# Safety_2019_V_3_0_uController.net
KiCad netlist of a schematic drawn in Altium Designer
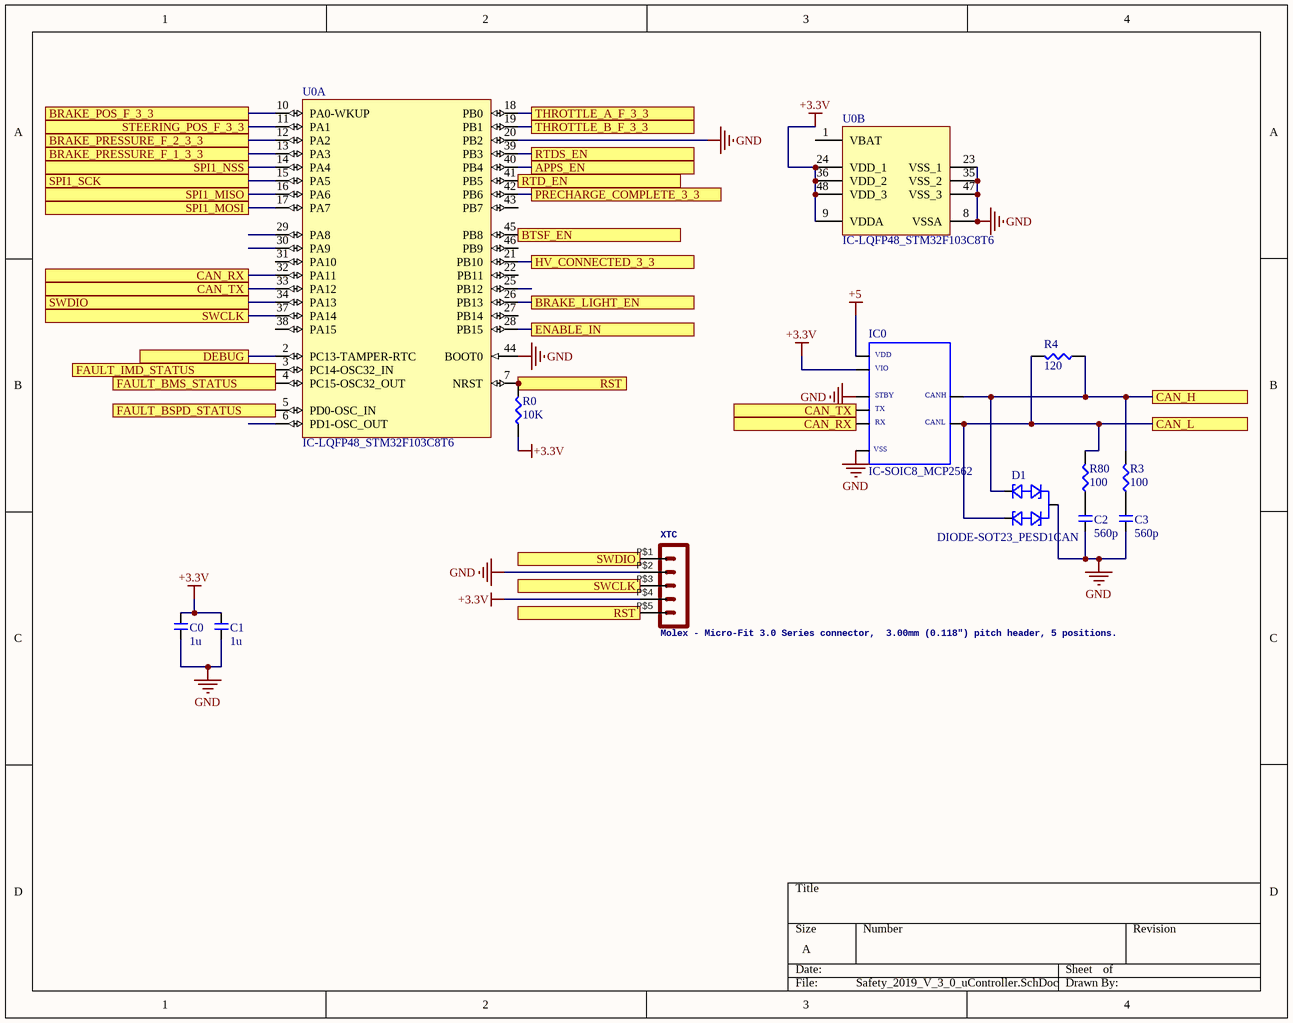
[diagram p0: Safety_2019_V_3_0_uController.SchDoc]

(export (version "E")
  (design (tool "Eeschema 10.0.6"))
  (components
    (comp (ref "C0")
      (value "1u")
      (footprint "CAP-0603")
      (libsource (lib "ife19_Elec_Library") (part "CAP-0603"))
    )
    (comp (ref "C1")
      (value "1u")
      (footprint "CAP-0603")
      (libsource (lib "ife19_Elec_Library") (part "CAP-0603"))
    )
    (comp (ref "C2")
      (value "560p")
      (footprint "CAP-0603")
      (libsource (lib "ife19_Elec_Library") (part "CAP-0603"))
    )
    (comp (ref "C3")
      (value "560p")
      (footprint "CAP-0603")
      (libsource (lib "ife19_Elec_Library") (part "CAP-0603"))
    )
    (comp (ref "D1")
      (value "DIODE-SOT23_PESD1CAN")
      (footprint "SOT23")
      (libsource (lib "ife19_Elec_Library") (part "DIODE-SOT23_PESD1CAN"))
    )
    (comp (ref "IC0")
      (value "IC-SOIC8_MCP2562")
      (footprint "SOIC8")
      (libsource (lib "ife19_Elec_Library") (part "IC-SOIC8_MCP2562"))
    )
    (comp (ref "R0")
      (value "10K")
      (footprint "RES-0603")
      (libsource (lib "ife19_Elec_Library") (part "RES-0603"))
    )
    (comp (ref "R3")
      (value "100")
      (footprint "RES-0603")
      (libsource (lib "ife19_Elec_Library") (part "RES-0603"))
    )
    (comp (ref "R4")
      (value "120")
      (footprint "RES-0603")
      (libsource (lib "ife19_Elec_Library") (part "RES-0603"))
    )
    (comp (ref "R80")
      (value "100")
      (footprint "RES-0603")
      (libsource (lib "ife19_Elec_Library") (part "RES-0603"))
    )
    (comp (ref "U0")
      (value "IC-LQFP48_STM32F103C8T6")
      (footprint "STM-LQFP48_M")
      (fields (field (name "PARTNUMBER") "STM32F103C8T6"))
      (libsource (lib "ife19_Elec_Library") (part "IC-LQFP48_STM32F103C8T6"))
    )
    (comp (ref "XTC")
      (value "Molex - Micro-Fit 3.0 Series connector,  3.00mm (0.118\") pitch header, 5 positions.")
      (footprint "POS5_254MM_MALE")
      (libsource (lib "ife19_Elec_Conn_Library") (part "POS5_254MM_MALE"))
    )
  )
  (nets
    (net (code "1") (name "+3.3V") (class "Default")
      (node (ref "C0") (pin "2") (pinfunction "2_2") (pintype "passive"))
      (node (ref "C1") (pin "2") (pinfunction "2_2") (pintype "passive"))
      (node (ref "IC0") (pin "5") (pinfunction "5_5") (pintype "passive"))
      (node (ref "R0") (pin "1") (pinfunction "1_1") (pintype "passive"))
      (node (ref "U0") (pin "24") (pinfunction "VDD_1_24") (pintype "power_in"))
      (node (ref "U0") (pin "36") (pinfunction "VDD_2_36") (pintype "power_in"))
      (node (ref "U0") (pin "48") (pinfunction "VDD_3_48") (pintype "power_in"))
      (node (ref "U0") (pin "9") (pinfunction "VDDA_9") (pintype "power_in"))
      (node (ref "XTC") (pin "P$4") (pinfunction "4_P$4") (pintype "passive"))
    )
    (net (code "2") (name "+5") (class "Default")
      (node (ref "IC0") (pin "3") (pinfunction "3_3") (pintype "passive"))
    )
    (net (code "3") (name "/APPS_EN") (class "Default")
      (node (ref "U0") (pin "40") (pinfunction "PB4_40") (pintype "bidirectional"))
    )
    (net (code "4") (name "/BRAKE_LIGHT_EN") (class "Default")
      (node (ref "U0") (pin "26") (pinfunction "PB13_26") (pintype "bidirectional"))
    )
    (net (code "5") (name "/BRAKE_POS_F_3_3") (class "Default")
      (node (ref "U0") (pin "10") (pinfunction "PA0-WKUP_10") (pintype "bidirectional"))
    )
    (net (code "6") (name "/BRAKE_PRESSURE_F_1_3_3") (class "Default")
      (node (ref "U0") (pin "13") (pinfunction "PA3_13") (pintype "bidirectional"))
    )
    (net (code "7") (name "/BRAKE_PRESSURE_F_2_3_3") (class "Default")
      (node (ref "U0") (pin "12") (pinfunction "PA2_12") (pintype "bidirectional"))
    )
    (net (code "8") (name "/BTSF_EN") (class "Default")
      (node (ref "U0") (pin "45") (pinfunction "PB8_45") (pintype "bidirectional"))
    )
    (net (code "9") (name "/CAN_H") (class "Default")
      (node (ref "D1") (pin "1") (pinfunction "CAN1_1") (pintype "passive"))
      (node (ref "IC0") (pin "7") (pinfunction "7_7") (pintype "passive"))
      (node (ref "R3") (pin "2") (pinfunction "2_2") (pintype "passive"))
      (node (ref "R4") (pin "1") (pinfunction "1_1") (pintype "passive"))
    )
    (net (code "10") (name "/CAN_L") (class "Default")
      (node (ref "D1") (pin "2") (pinfunction "CAN2_2") (pintype "passive"))
      (node (ref "IC0") (pin "6") (pinfunction "6_6") (pintype "passive"))
      (node (ref "R4") (pin "2") (pinfunction "2_2") (pintype "passive"))
      (node (ref "R80") (pin "2") (pinfunction "2_2") (pintype "passive"))
    )
    (net (code "11") (name "/CAN_RX") (class "Default")
      (node (ref "IC0") (pin "4") (pinfunction "4_4") (pintype "passive"))
      (node (ref "U0") (pin "32") (pinfunction "PA11_32") (pintype "bidirectional"))
    )
    (net (code "12") (name "/CAN_TX") (class "Default")
      (node (ref "IC0") (pin "1") (pinfunction "1_1") (pintype "passive"))
      (node (ref "U0") (pin "33") (pinfunction "PA12_33") (pintype "bidirectional"))
    )
    (net (code "13") (name "/DEBUG") (class "Default")
      (node (ref "U0") (pin "2") (pinfunction "PC13-TAMPER-RTC_2") (pintype "bidirectional"))
    )
    (net (code "14") (name "/ENABLE_IN") (class "Default")
      (node (ref "U0") (pin "28") (pinfunction "PB15_28") (pintype "bidirectional"))
    )
    (net (code "15") (name "/FAULT_BMS_STATUS") (class "Default")
      (node (ref "U0") (pin "4") (pinfunction "PC15-OSC32_OUT_4") (pintype "bidirectional"))
    )
    (net (code "16") (name "/FAULT_BSPD_STATUS") (class "Default")
      (node (ref "U0") (pin "5") (pinfunction "PD0-OSC_IN_5") (pintype "bidirectional"))
    )
    (net (code "17") (name "/FAULT_IMD_STATUS") (class "Default")
      (node (ref "U0") (pin "3") (pinfunction "PC14-OSC32_IN_3") (pintype "bidirectional"))
    )
    (net (code "18") (name "/HV_CONNECTED_3_3") (class "Default")
      (node (ref "U0") (pin "21") (pinfunction "PB10_21") (pintype "bidirectional"))
    )
    (net (code "19") (name "/PRECHARGE_COMPLETE_3_3") (class "Default")
      (node (ref "U0") (pin "42") (pinfunction "PB6_42") (pintype "bidirectional"))
    )
    (net (code "20") (name "/RST") (class "Default")
      (node (ref "R0") (pin "2") (pinfunction "2_2") (pintype "passive"))
      (node (ref "U0") (pin "7") (pinfunction "NRST_7") (pintype "bidirectional"))
      (node (ref "XTC") (pin "P$5") (pinfunction "5_P$5") (pintype "passive"))
    )
    (net (code "21") (name "/RTDS_EN") (class "Default")
      (node (ref "U0") (pin "39") (pinfunction "PB3_39") (pintype "bidirectional"))
    )
    (net (code "22") (name "/RTD_EN") (class "Default")
      (node (ref "U0") (pin "41") (pinfunction "PB5_41") (pintype "bidirectional"))
    )
    (net (code "23") (name "/SPI1_MISO") (class "Default")
      (node (ref "U0") (pin "16") (pinfunction "PA6_16") (pintype "bidirectional"))
    )
    (net (code "24") (name "/SPI1_MOSI") (class "Default")
      (node (ref "U0") (pin "17") (pinfunction "PA7_17") (pintype "bidirectional"))
    )
    (net (code "25") (name "/SPI1_NSS") (class "Default")
      (node (ref "U0") (pin "14") (pinfunction "PA4_14") (pintype "bidirectional"))
    )
    (net (code "26") (name "/SPI1_SCK") (class "Default")
      (node (ref "U0") (pin "15") (pinfunction "PA5_15") (pintype "bidirectional"))
    )
    (net (code "27") (name "/STEERING_POS_F_3_3") (class "Default")
      (node (ref "U0") (pin "11") (pinfunction "PA1_11") (pintype "bidirectional"))
    )
    (net (code "28") (name "/SWCLK") (class "Default")
      (node (ref "U0") (pin "37") (pinfunction "PA14_37") (pintype "bidirectional"))
      (node (ref "XTC") (pin "P$3") (pinfunction "3_P$3") (pintype "passive"))
    )
    (net (code "29") (name "/SWDIO") (class "Default")
      (node (ref "U0") (pin "34") (pinfunction "PA13_34") (pintype "bidirectional"))
      (node (ref "XTC") (pin "P$1") (pinfunction "1_P$1") (pintype "passive"))
    )
    (net (code "30") (name "/THROTTLE_A_F_3_3") (class "Default")
      (node (ref "U0") (pin "18") (pinfunction "PB0_18") (pintype "bidirectional"))
    )
    (net (code "31") (name "/THROTTLE_B_F_3_3") (class "Default")
      (node (ref "U0") (pin "19") (pinfunction "PB1_19") (pintype "bidirectional"))
    )
    (net (code "32") (name "GND") (class "Default")
      (node (ref "C0") (pin "1") (pinfunction "1_1") (pintype "passive"))
      (node (ref "C1") (pin "1") (pinfunction "1_1") (pintype "passive"))
      (node (ref "C2") (pin "1") (pinfunction "1_1") (pintype "passive"))
      (node (ref "C3") (pin "1") (pinfunction "1_1") (pintype "passive"))
      (node (ref "D1") (pin "3") (pinfunction "G_3") (pintype "passive"))
      (node (ref "IC0") (pin "2") (pinfunction "2_2") (pintype "passive"))
      (node (ref "IC0") (pin "8") (pinfunction "8_8") (pintype "passive"))
      (node (ref "U0") (pin "20") (pinfunction "PB2_20") (pintype "bidirectional"))
      (node (ref "U0") (pin "23") (pinfunction "VSS_1_23") (pintype "power_in"))
      (node (ref "U0") (pin "35") (pinfunction "VSS_2_35") (pintype "power_in"))
      (node (ref "U0") (pin "44") (pinfunction "BOOT0_44") (pintype "input"))
      (node (ref "U0") (pin "47") (pinfunction "VSS_3_47") (pintype "power_in"))
      (node (ref "U0") (pin "8") (pinfunction "VSSA_8") (pintype "power_in"))
      (node (ref "XTC") (pin "P$2") (pinfunction "2_P$2") (pintype "passive"))
    )
    (net (code "33") (name "Net-(C2-Pad2)") (class "Default")
      (node (ref "C2") (pin "2") (pinfunction "2_2") (pintype "passive"))
      (node (ref "R80") (pin "1") (pinfunction "1_1") (pintype "passive"))
    )
    (net (code "34") (name "Net-(C3-Pad2)") (class "Default")
      (node (ref "C3") (pin "2") (pinfunction "2_2") (pintype "passive"))
      (node (ref "R3") (pin "1") (pinfunction "1_1") (pintype "passive"))
    )
    (net (code "35") (name "unconnected-(U0A-PA8-Pad29)") (class "Default")
      (node (ref "U0") (pin "29") (pinfunction "PA8_29") (pintype "bidirectional"))
    )
    (net (code "36") (name "unconnected-(U0A-PA9-Pad30)") (class "Default")
      (node (ref "U0") (pin "30") (pinfunction "PA9_30") (pintype "bidirectional"))
    )
    (net (code "37") (name "unconnected-(U0A-PA10-Pad31)") (class "Default")
      (node (ref "U0") (pin "31") (pinfunction "PA10_31") (pintype "bidirectional"))
    )
    (net (code "38") (name "unconnected-(U0A-PA15-Pad38)") (class "Default")
      (node (ref "U0") (pin "38") (pinfunction "PA15_38") (pintype "bidirectional"))
    )
    (net (code "39") (name "unconnected-(U0A-PB7-Pad43)") (class "Default")
      (node (ref "U0") (pin "43") (pinfunction "PB7_43") (pintype "bidirectional"))
    )
    (net (code "40") (name "unconnected-(U0A-PB9-Pad46)") (class "Default")
      (node (ref "U0") (pin "46") (pinfunction "PB9_46") (pintype "bidirectional"))
    )
    (net (code "41") (name "unconnected-(U0A-PB11-Pad22)") (class "Default")
      (node (ref "U0") (pin "22") (pinfunction "PB11_22") (pintype "bidirectional"))
    )
    (net (code "42") (name "unconnected-(U0A-PB12-Pad25)") (class "Default")
      (node (ref "U0") (pin "25") (pinfunction "PB12_25") (pintype "bidirectional"))
    )
    (net (code "43") (name "unconnected-(U0A-PB14-Pad27)") (class "Default")
      (node (ref "U0") (pin "27") (pinfunction "PB14_27") (pintype "bidirectional"))
    )
    (net (code "44") (name "unconnected-(U0A-PD1-OSC_OUT-Pad6)") (class "Default")
      (node (ref "U0") (pin "6") (pinfunction "PD1-OSC_OUT_6") (pintype "bidirectional"))
    )
    (net (code "45") (name "unconnected-(U0B-VBAT-Pad1)") (class "Default")
      (node (ref "U0") (pin "1") (pinfunction "VBAT_1") (pintype "power_in"))
    )
  )
)
